# PowerCircuit.net
KiCad netlist of a schematic drawn in Altium Designer
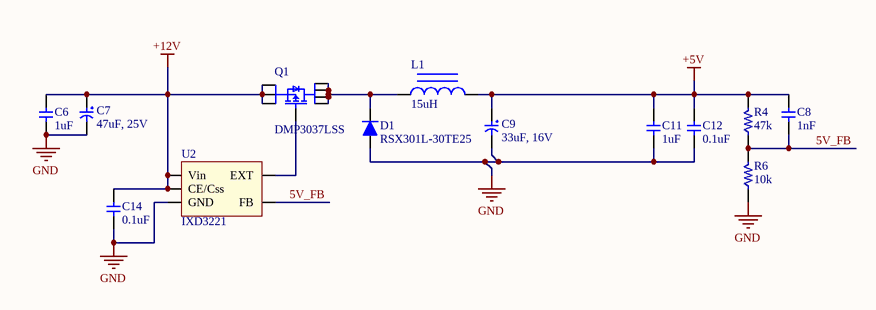
[diagram p0: PowerCircuit.SchDoc]

(export (version "E")
  (design (tool "Eeschema 10.0.6"))
  (components
    (comp (ref "C6")
      (value "1uF")
      (footprint "0805")
      (description "Generic capacitor")
      (fields (field (name "Comment") "Generic Capacitor"))
      (libsource (lib "PowerCircuit") (part "Capacitor"))
    )
    (comp (ref "C7")
      (value "47uF, 25V")
      (footprint "Cap 6.3mm dia 5.4mm Height")
      (description "Polorised capacitor 47uF, 25V")
      (libsource (lib "PowerCircuit") (part "865080443007"))
    )
    (comp (ref "C8")
      (value "1nF")
      (footprint "0805")
      (description "Generic capacitor")
      (fields (field (name "Comment") "Generic Capacitor"))
      (libsource (lib "PowerCircuit") (part "Capacitor"))
    )
    (comp (ref "C9")
      (value "33uF, 16V")
      (footprint "Cap 6.3mm dia 5.4mm Height")
      (description "Polorised capacitor 33uF, 16V")
      (libsource (lib "PowerCircuit") (part "865060343003"))
    )
    (comp (ref "C11")
      (value "1uF")
      (footprint "0805")
      (description "Generic capacitor")
      (fields (field (name "Comment") "Generic Capacitor"))
      (libsource (lib "PowerCircuit") (part "Capacitor"))
    )
    (comp (ref "C12")
      (value "0.1uF")
      (footprint "0805")
      (description "Generic capacitor")
      (fields (field (name "Comment") "Generic Capacitor"))
      (libsource (lib "PowerCircuit") (part "Capacitor"))
    )
    (comp (ref "C14")
      (value "0.1uF")
      (footprint "0805")
      (description "Generic capacitor")
      (fields (field (name "Comment") "Generic Capacitor"))
      (libsource (lib "PowerCircuit") (part "Capacitor"))
    )
    (comp (ref "D1")
      (value "RSX301L-30TE25")
      (footprint "SMA_diode")
      (description "DIODE SCHOTTKY 30V 3A")
      (libsource (lib "PowerCircuit") (part "RSX301L-30TE25"))
    )
    (comp (ref "L1")
      (value "15uH")
      (footprint "SRN8040")
      (description "INDUCTOR 15uH 2.4A 70mOHMS SMD")
      (libsource (lib "PowerCircuit") (part "SRN8040-150MCT"))
    )
    (comp (ref "Q1")
      (value "DMP3037LSS")
      (footprint "SOIC-8-PP")
      (description "P-CHANNEL ENHANCEMENT MODE MOSFET")
      (libsource (lib "PowerCircuit") (part "DMP3037LSS"))
    )
    (comp (ref "R4")
      (value "47k")
      (footprint "0805")
      (description "Generic Resistor")
      (fields (field (name "Comment") "Resistor"))
      (libsource (lib "PowerCircuit") (part "Resistor"))
    )
    (comp (ref "R6")
      (value "10k")
      (footprint "0805")
      (description "Generic Resistor")
      (fields (field (name "Comment") "Resistor"))
      (libsource (lib "PowerCircuit") (part "Resistor"))
    )
    (comp (ref "U2")
      (value "IXD3221")
      (footprint "SOT23-5")
      (description "IC REG CTRLR BUCK SOT25")
      (libsource (lib "PowerCircuit") (part "IXD3221"))
    )
  )
  (nets
    (net (code "1") (name "+5V") (class "Default")
      (node (ref "C11") (pin "1") (pinfunction "1_1") (pintype "passive"))
      (node (ref "C12") (pin "1") (pinfunction "1_1") (pintype "passive"))
      (node (ref "C8") (pin "1") (pinfunction "1_1") (pintype "passive"))
      (node (ref "C9") (pin "1") (pinfunction "1_1") (pintype "passive"))
      (node (ref "L1") (pin "2") (pinfunction "2_2") (pintype "passive"))
      (node (ref "R4") (pin "2") (pinfunction "2_2") (pintype "passive"))
    )
    (net (code "2") (name "+12V") (class "Default")
      (node (ref "C14") (pin "1") (pinfunction "1_1") (pintype "passive"))
      (node (ref "C6") (pin "2") (pinfunction "2_2") (pintype "passive"))
      (node (ref "C7") (pin "1") (pinfunction "1_1") (pintype "passive"))
      (node (ref "Q1") (pin "1") (pinfunction "S_1") (pintype "passive"))
      (node (ref "Q1") (pin "2") (pinfunction "S_2") (pintype "passive"))
      (node (ref "Q1") (pin "3") (pinfunction "S_3") (pintype "passive"))
      (node (ref "U2") (pin "1") (pinfunction "CE/Css_1") (pintype "passive"))
      (node (ref "U2") (pin "5") (pinfunction "Vin_5") (pintype "passive"))
    )
    (net (code "3") (name "/5V_FB") (class "Default")
      (node (ref "C8") (pin "2") (pinfunction "2_2") (pintype "passive"))
      (node (ref "R4") (pin "1") (pinfunction "1_1") (pintype "passive"))
      (node (ref "R6") (pin "2") (pinfunction "2_2") (pintype "passive"))
      (node (ref "U2") (pin "3") (pinfunction "FB_3") (pintype "passive"))
    )
    (net (code "4") (name "GND") (class "Default")
      (node (ref "C11") (pin "2") (pinfunction "2_2") (pintype "passive"))
      (node (ref "C12") (pin "2") (pinfunction "2_2") (pintype "passive"))
      (node (ref "C14") (pin "2") (pinfunction "2_2") (pintype "passive"))
      (node (ref "C6") (pin "1") (pinfunction "1_1") (pintype "passive"))
      (node (ref "C7") (pin "2") (pinfunction "2_2") (pintype "passive"))
      (node (ref "C9") (pin "2") (pinfunction "2_2") (pintype "passive"))
      (node (ref "D1") (pin "1") (pinfunction "1_1") (pintype "passive"))
      (node (ref "R6") (pin "1") (pinfunction "1_1") (pintype "passive"))
      (node (ref "U2") (pin "2") (pinfunction "GND_2") (pintype "passive"))
    )
    (net (code "5") (name "Net-(D1-Pad2)") (class "Default")
      (node (ref "D1") (pin "2") (pinfunction "2_2") (pintype "passive"))
      (node (ref "L1") (pin "1") (pinfunction "1_1") (pintype "passive"))
      (node (ref "Q1") (pin "5") (pinfunction "D_5") (pintype "passive"))
      (node (ref "Q1") (pin "6") (pinfunction "D_6") (pintype "passive"))
      (node (ref "Q1") (pin "7") (pinfunction "D_7") (pintype "passive"))
      (node (ref "Q1") (pin "8") (pinfunction "D_8") (pintype "passive"))
    )
    (net (code "6") (name "Net-(Q1-G)") (class "Default")
      (node (ref "Q1") (pin "4") (pinfunction "G_4") (pintype "passive"))
      (node (ref "U2") (pin "4") (pinfunction "EXT_4") (pintype "passive"))
    )
  )
)
